# TPS5530RTE_Schematic.net
KiCad netlist of a schematic drawn in Altium Designer
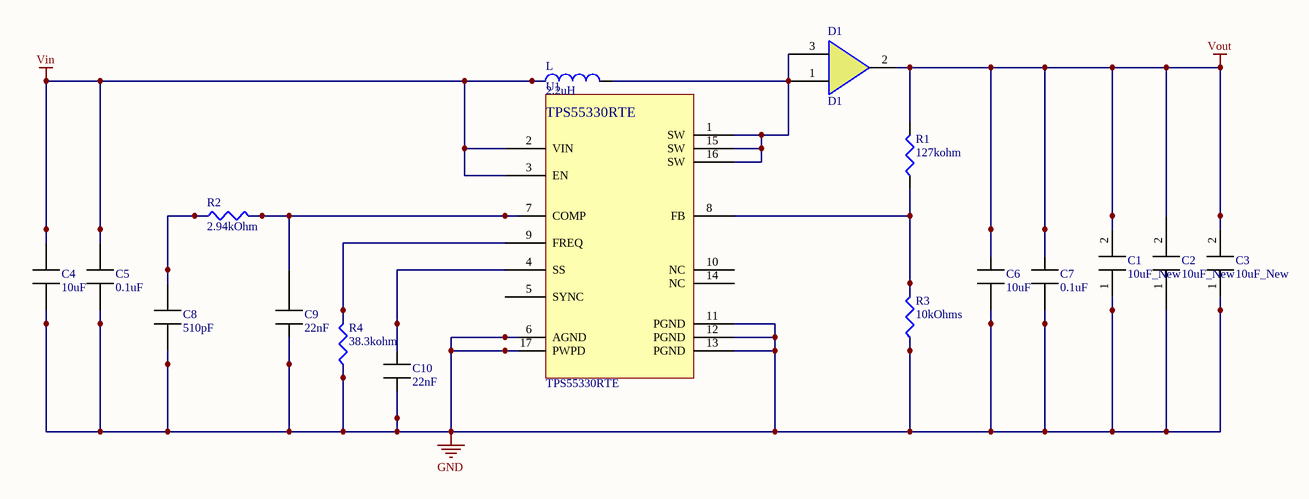
[diagram p0: TPS5530RTE_Schematic.SchDoc]

(export (version "E")
  (design (tool "Eeschema 10.0.6"))
  (components
    (comp (ref "C1")
      (value "10uF_New")
      (footprint "CAPPM7343X310N")
      (description "CAP TANT 10UF 35V 20% 2917")
      (fields
        (field (name "MANUFACTURER") "KEMET")
        (field (name "MANUFACTURER PART NUMBER") "T495D106M035ATE125")
      )
      (libsource (lib "TPSM84824MOL_PCB_Library") (part "T495D106M035ATE125"))
    )
    (comp (ref "C2")
      (value "10uF_New")
      (footprint "CAPPM7343X310N")
      (description "CAP TANT 10UF 35V 20% 2917")
      (fields
        (field (name "MANUFACTURER") "KEMET")
        (field (name "MANUFACTURER PART NUMBER") "T495D106M035ATE125")
      )
      (libsource (lib "TPSM84824MOL_PCB_Library") (part "T495D106M035ATE125"))
    )
    (comp (ref "C3")
      (value "10uF_New")
      (footprint "CAPPM7343X310N")
      (description "CAP TANT 10UF 35V 20% 2917")
      (fields
        (field (name "MANUFACTURER") "KEMET")
        (field (name "MANUFACTURER PART NUMBER") "T495D106M035ATE125")
      )
      (libsource (lib "TPSM84824MOL_PCB_Library") (part "T495D106M035ATE125"))
    )
    (comp (ref "C4")
      (value "10uF")
      (footprint "C/R1206")
      (description "Cap Ceramic 10uF 16V X5R 10% SMD 1206 85C T/R")
      (fields
        (field (name "MANUFACTURER") "Murata")
        (field (name "MANUFACTURER PART NUMBER") "GRM31CR61C106KA88L")
      )
      (libsource (lib "TPS55330RTE_Schematic_Library") (part "GRM31CR61C106KA88L"))
    )
    (comp (ref "C5")
      (value "0.1uF")
      (footprint "C/R0402")
      (description "CAP CER 0.1UF 16V X7R 0402")
      (fields
        (field (name "MANUFACTURER") "Murata")
        (field (name "MANUFACTURER PART NUMBER") "GRM155R71C104KA88D")
      )
      (libsource (lib "TPS55330RTE_Schematic_Library") (part "GRM155R71C104KA88D"))
    )
    (comp (ref "C6")
      (value "10uF")
      (footprint "C/R0805")
      (description "TDK - CGA6P3X7S1H106K250AB - CAP, 10µF, 50V, 10%, X7S, 1210")
      (fields
        (field (name "MANUFACTURER") "TDK")
        (field (name "MANUFACTURER PART NUMBER") "CGA6P3X7S1H106K250AB")
      )
      (libsource (lib "TPS55330RTE_Schematic_Library") (part "CGA6P3X7S1H106K250AB"))
    )
    (comp (ref "C7")
      (value "0.1uF")
      (footprint "C/R0402")
      (description "CAP CER 0.1UF 16V X7R 0402")
      (fields
        (field (name "MANUFACTURER") "Murata")
        (field (name "MANUFACTURER PART NUMBER") "GRM155R71C104KA88D")
      )
      (libsource (lib "TPS55330RTE_Schematic_Library") (part "GRM155R71C104KA88D"))
    )
    (comp (ref "C8")
      (value "510pF")
      (footprint "C/R0402")
      (description "Cap Ceramic 510pF 50V C0G 2% SMD 0402 125C Paper T/R")
      (fields
        (field (name "MANUFACTURER") "Murata")
        (field (name "MANUFACTURER PART NUMBER") "GRM1555C1H511GA01D")
      )
      (libsource (lib "TPS55330RTE_Schematic_Library") (part "GRM1555C1H511GA01D"))
    )
    (comp (ref "C9")
      (value "22nF")
      (footprint "C/R0805")
      (description "TDK - CGA4J2C0G1H223J125AA - KONDENSATOR 0.022µF 50V 5% C0G/NP0 0805")
      (fields
        (field (name "MANUFACTURER") "TDK")
        (field (name "MANUFACTURER PART NUMBER") "CGA4J2C0G1H223J125AA")
      )
      (libsource (lib "TPS55330RTE_Schematic_Library") (part "CGA4J2C0G1H223J125AA"))
    )
    (comp (ref "C10")
      (value "22nF")
      (footprint "C/R0805")
      (description "KEMET 22nF Multilayer Ceramic Capacitor (MLCC) 50V dc 10% X7R dielectric max op. temp. 125C")
      (fields
        (field (name "MANUFACTURER") "KEMET")
        (field (name "MANUFACTURER PART NUMBER") "C0805C223K5RAC")
      )
      (libsource (lib "TPS55330RTE_Schematic_Library") (part "C0805C223K5RAC"))
    )
    (comp (ref "D1")
      (value "D1")
      (footprint "D1")
      (description "DIODE SCHOTTKY 60V 7A POWERDI5")
      (fields (field (name "MANUFACTURER") "Diodes") (field (name "MANUFACTURER PART NUMBER") "PDS760-13"))
      (libsource (lib "TPS55330RTE_Schematic_Library") (part "PDS760-13"))
    )
    (comp (ref "L")
      (value "2.2uH")
      (footprint "L1")
      (description "Fixed Inductors 2.2uH 20%")
      (fields
        (field (name "MANUFACTURER") "Vishay Dale")
        (field (name "MANUFACTURER PART NUMBER") "IHLP2525EZER2R2M01")
      )
      (libsource (lib "TPS55330RTE_Schematic_Library") (part "IHLP2525EZER2R2M01"))
    )
    (comp (ref "R1")
      (value "127kohm")
      (footprint "C/R0805")
      (description "RES SMD 127K OHM 0.1% 1/8W 0805")
      (fields
        (field (name "MANUFACTURER") "Panasonic")
        (field (name "MANUFACTURER PART NUMBER") "ERA-6AEB1273V")
      )
      (libsource (lib "TPS55330RTE_Schematic_Library") (part "ERA-6AEB1273V"))
    )
    (comp (ref "R2")
      (value "2.94kOhm")
      (footprint "C/R0805")
      (description "RES SMD 2.94K OHM 0.1% 1/8W 0805")
      (fields
        (field (name "MANUFACTURER") "Panasonic")
        (field (name "MANUFACTURER PART NUMBER") "ERA-6AEB2941V")
      )
      (libsource (lib "TPS55330RTE_Schematic_Library") (part "ERA-6AEB2941V"))
    )
    (comp (ref "R3")
      (value "10kOhms")
      (footprint "C/R0805")
      (description "Res Thick Film 0805 10K Ohm 1% 0.125W(1/8W) ±100ppm/C Molded SMD Automotive Paper T/R")
      (fields
        (field (name "MANUFACTURER") "Vishay Dale")
        (field (name "MANUFACTURER PART NUMBER") "CRCW080510K0FKEC")
      )
      (libsource (lib "TPS55330RTE_Schematic_Library") (part "CRCW080510K0FKEC"))
    )
    (comp (ref "R4")
      (value "38.3kohm")
      (footprint "C/R0805")
      (description "RES SMD 38.3K OHM 0.1% 1/8W 0805")
      (fields
        (field (name "MANUFACTURER") "Panasonic")
        (field (name "MANUFACTURER PART NUMBER") "ERA-6AEB3832V")
      )
      (libsource (lib "TPS55330RTE_Schematic_Library") (part "ERA-6AEB3832V"))
    )
    (comp (ref "U1")
      (value "TPS55330RTE")
      (footprint "TPS55330")
      (fields
        (field (name "MANUFACTURER") "Texas Instruments")
        (field (name "MANUFACTURER PART NUMBER") "TPS55330RTER")
      )
      (libsource (lib "TPS55330RTE_Schematic_Library") (part "TPS55330RTE"))
    )
  )
  (nets
    (net (code "1") (name "GND") (class "Default")
      (node (ref "C1") (pin "1") (pinfunction "1_1") (pintype "passive"))
      (node (ref "C10") (pin "1") (pinfunction "1_1") (pintype "passive"))
      (node (ref "C2") (pin "1") (pinfunction "1_1") (pintype "passive"))
      (node (ref "C3") (pin "1") (pinfunction "1_1") (pintype "passive"))
      (node (ref "C4") (pin "2") (pinfunction "2_2") (pintype "passive"))
      (node (ref "C5") (pin "2") (pinfunction "2_2") (pintype "passive"))
      (node (ref "C6") (pin "2") (pinfunction "2_2") (pintype "passive"))
      (node (ref "C7") (pin "1") (pinfunction "1_1") (pintype "passive"))
      (node (ref "C8") (pin "2") (pinfunction "2_2") (pintype "passive"))
      (node (ref "C9") (pin "1") (pinfunction "1_1") (pintype "passive"))
      (node (ref "R3") (pin "1") (pinfunction "1_1") (pintype "passive"))
      (node (ref "R4") (pin "1") (pinfunction "1_1") (pintype "passive"))
      (node (ref "U1") (pin "11") (pinfunction "PGND_11") (pintype "passive"))
      (node (ref "U1") (pin "12") (pinfunction "PGND_12") (pintype "passive"))
      (node (ref "U1") (pin "13") (pinfunction "PGND_13") (pintype "passive"))
      (node (ref "U1") (pin "17") (pinfunction "PWPD_17") (pintype "passive"))
      (node (ref "U1") (pin "6") (pinfunction "AGND_6") (pintype "passive"))
    )
    (net (code "2") (name "Net-(C8-Pad1)") (class "Default")
      (node (ref "C8") (pin "1") (pinfunction "1_1") (pintype "passive"))
      (node (ref "R2") (pin "1") (pinfunction "1_1") (pintype "passive"))
    )
    (net (code "3") (name "Net-(D1-Pad1)") (class "Default")
      (node (ref "D1") (pin "1") (pinfunction "1_1") (pintype "passive"))
      (node (ref "D1") (pin "3") (pinfunction "3_3") (pintype "passive"))
      (node (ref "L") (pin "2") (pinfunction "2_2") (pintype "passive"))
      (node (ref "U1") (pin "1") (pinfunction "SW_1") (pintype "passive"))
      (node (ref "U1") (pin "15") (pinfunction "SW_15") (pintype "passive"))
      (node (ref "U1") (pin "16") (pinfunction "SW_16") (pintype "passive"))
    )
    (net (code "4") (name "Net-(U1-COMP)") (class "Default")
      (node (ref "C9") (pin "2") (pinfunction "2_2") (pintype "passive"))
      (node (ref "R2") (pin "2") (pinfunction "2_2") (pintype "passive"))
      (node (ref "U1") (pin "7") (pinfunction "COMP_7") (pintype "passive"))
    )
    (net (code "5") (name "Net-(U1-FB)") (class "Default")
      (node (ref "R1") (pin "1") (pinfunction "1_1") (pintype "passive"))
      (node (ref "R3") (pin "2") (pinfunction "2_2") (pintype "passive"))
      (node (ref "U1") (pin "8") (pinfunction "FB_8") (pintype "passive"))
    )
    (net (code "6") (name "Net-(U1-FREQ)") (class "Default")
      (node (ref "R4") (pin "2") (pinfunction "2_2") (pintype "passive"))
      (node (ref "U1") (pin "9") (pinfunction "FREQ_9") (pintype "passive"))
    )
    (net (code "7") (name "Net-(U1-SS)") (class "Default")
      (node (ref "C10") (pin "2") (pinfunction "2_2") (pintype "passive"))
      (node (ref "U1") (pin "4") (pinfunction "SS_4") (pintype "passive"))
    )
    (net (code "8") (name "Vin") (class "Default")
      (node (ref "C4") (pin "1") (pinfunction "1_1") (pintype "passive"))
      (node (ref "C5") (pin "1") (pinfunction "1_1") (pintype "passive"))
      (node (ref "L") (pin "1") (pinfunction "1_1") (pintype "passive"))
      (node (ref "U1") (pin "2") (pinfunction "VIN_2") (pintype "passive"))
      (node (ref "U1") (pin "3") (pinfunction "EN_3") (pintype "passive"))
    )
    (net (code "9") (name "Vout") (class "Default")
      (node (ref "C1") (pin "2") (pinfunction "2_2") (pintype "passive"))
      (node (ref "C2") (pin "2") (pinfunction "2_2") (pintype "passive"))
      (node (ref "C3") (pin "2") (pinfunction "2_2") (pintype "passive"))
      (node (ref "C6") (pin "1") (pinfunction "1_1") (pintype "passive"))
      (node (ref "C7") (pin "2") (pinfunction "2_2") (pintype "passive"))
      (node (ref "D1") (pin "2") (pinfunction "2_2") (pintype "passive"))
      (node (ref "R1") (pin "2") (pinfunction "2_2") (pintype "passive"))
    )
    (net (code "10") (name "unconnected-(U1-NC-Pad10)") (class "Default")
      (node (ref "U1") (pin "10") (pinfunction "NC_10") (pintype "passive"))
    )
    (net (code "11") (name "unconnected-(U1-NC-Pad14)") (class "Default")
      (node (ref "U1") (pin "14") (pinfunction "NC_14") (pintype "passive"))
    )
    (net (code "12") (name "unconnected-(U1-SYNC-Pad5)") (class "Default")
      (node (ref "U1") (pin "5") (pinfunction "SYNC_5") (pintype "passive"))
    )
  )
)
